# main.net
KiCad netlist of a schematic drawn in Altium Designer
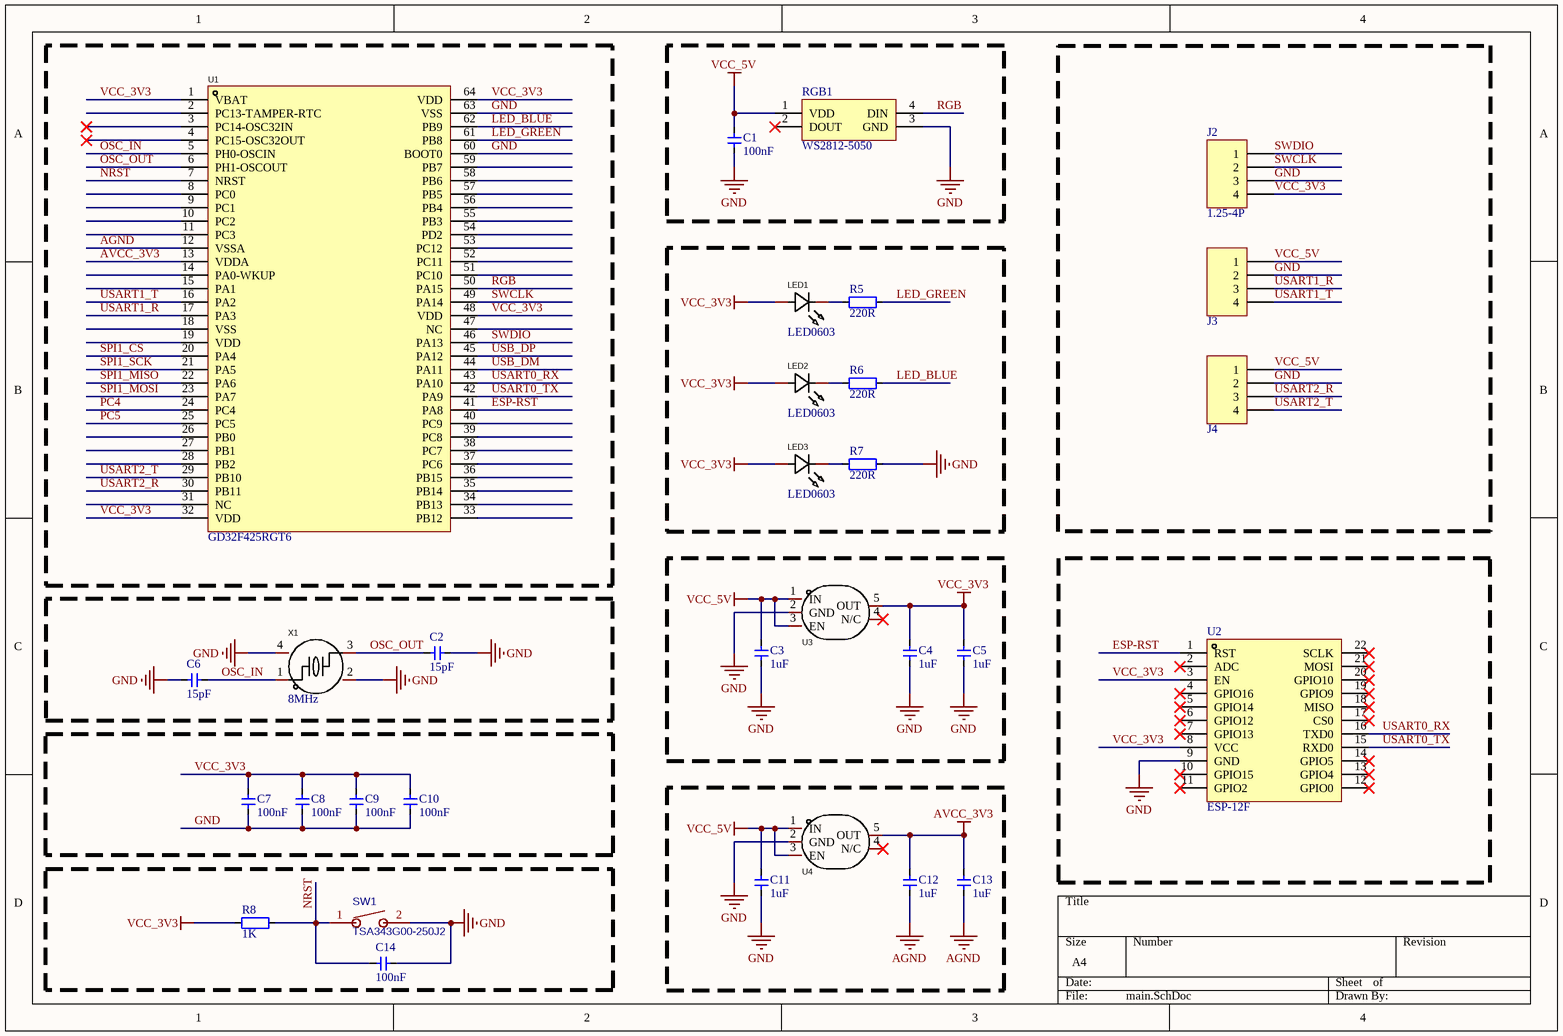
[diagram p0: main.SchDoc]

(export (version "E")
  (design (tool "Eeschema 10.0.6"))
  (components
    (comp (ref "C1") (value "100nF") (footprint "C0603") (libsource (lib "vesc6") (part "C0603")))
    (comp (ref "C2") (value "15pF") (footprint "C0603") (libsource (lib "vesc6") (part "C0603")))
    (comp (ref "C3") (value "1uF") (footprint "C0603") (libsource (lib "vesc6") (part "C0603")))
    (comp (ref "C4") (value "1uF") (footprint "C0603") (libsource (lib "vesc6") (part "C0603")))
    (comp (ref "C5") (value "1uF") (footprint "C0603") (libsource (lib "vesc6") (part "C0603")))
    (comp (ref "C6") (value "15pF") (footprint "C0603") (libsource (lib "vesc6") (part "C0603")))
    (comp (ref "C7") (value "100nF") (footprint "C0603") (libsource (lib "vesc6") (part "C0603")))
    (comp (ref "C8") (value "100nF") (footprint "C0603") (libsource (lib "vesc6") (part "C0603")))
    (comp (ref "C9") (value "100nF") (footprint "C0603") (libsource (lib "vesc6") (part "C0603")))
    (comp (ref "C10") (value "100nF") (footprint "C0603") (libsource (lib "vesc6") (part "C0603")))
    (comp (ref "C11") (value "1uF") (footprint "C0603") (libsource (lib "vesc6") (part "C0603")))
    (comp (ref "C12") (value "1uF") (footprint "C0603") (libsource (lib "vesc6") (part "C0603")))
    (comp (ref "C13") (value "1uF") (footprint "C0603") (libsource (lib "vesc6") (part "C0603")))
    (comp (ref "C14") (value "100nF") (footprint "C0603") (libsource (lib "vesc6") (part "C0603")))
    (comp (ref "J2")
      (value "1.25-4P")
      (footprint "CONN-SMD_1.25-4PWT")
      (libsource (lib "Connector") (part "A1.25-4P"))
    )
    (comp (ref "J3")
      (value "GH1.25-W-4P")
      (footprint "CONN-SMD_4P-P1.25_X1251WRS-04HF-LPSW")
      (libsource (lib "Connector") (part "GH1.25-W-4P"))
    )
    (comp (ref "J4")
      (value "GH1.25-W-4P")
      (footprint "CONN-SMD_4P-P1.25_X1251WRS-04HF-LPSW")
      (libsource (lib "Connector") (part "GH1.25-W-4P"))
    )
    (comp (ref "LED1")
      (value "LED0603")
      (footprint "LED0603-BLUE")
      (fields (field (name "MANUFACTURER") "VISHAY(威世)") (field (name "MANUFACTURER PART") "VLMTG1401-GS08"))
      (libsource (lib "vesc6") (part "LED0603"))
    )
    (comp (ref "LED2")
      (value "LED0603")
      (footprint "LED0603-BLUE")
      (fields (field (name "MANUFACTURER") "VISHAY(威世)") (field (name "MANUFACTURER PART") "VLMTG1401-GS08"))
      (libsource (lib "vesc6") (part "LED0603"))
    )
    (comp (ref "LED3")
      (value "LED0603")
      (footprint "LED0603-BLUE")
      (fields (field (name "MANUFACTURER") "VISHAY(威世)") (field (name "MANUFACTURER PART") "VLMTG1401-GS08"))
      (libsource (lib "vesc6") (part "LED0603"))
    )
    (comp (ref "R5") (value "220R") (footprint "R0603") (libsource (lib "vesc6") (part "R0603")))
    (comp (ref "R6") (value "220R") (footprint "R0603") (libsource (lib "vesc6") (part "R0603")))
    (comp (ref "R7") (value "220R") (footprint "R0603") (libsource (lib "vesc6") (part "R0603")))
    (comp (ref "R8") (value "1K") (footprint "R0603") (libsource (lib "vesc6") (part "R0603")))
    (comp (ref "RGB1")
      (value "WS2812-5050")
      (footprint "LED-SMD_4P-L5.0-W5.0-TL_WS2812B-B")
      (libsource (lib "other") (part "WS2812-5050"))
    )
    (comp (ref "SW1")
      (value "TSA343G00-250J2")
      (footprint "SW-SMD_L4.0-W2.9-LS5.0")
      (description "贴片轻触开关")
      (fields (field (name "BOM_SUPPLIER PART") "C354946") (field (name "CONTRIBUTOR") "LCSC"))
      (libsource (lib "MyLib") (part "TSA343G00-250J2"))
    )
    (comp (ref "U1")
      (value "GD32F425RGT6")
      (footprint "LQFP-64_L10.0-W10.0-P0.50-LS12.0-BL - duplicate")
      (fields (field (name "MANUFACTURER") "GigaDevice(兆易创新)"))
      (libsource (lib "IC") (part "GD32F425RGT6"))
    )
    (comp (ref "U2")
      (value "ESP-12F")
      (footprint "WIFIM-SMD_ESP-12F-ESP8266MOD")
      (libsource (lib "IC") (part "ESP-12F"))
    )
    (comp (ref "U3")
      (value "LP5907")
      (footprint "SOT-23-5_L2.9-W1.6-P0.95-LS2.8-BR")
      (fields
        (field (name "MANUFACTURER") "TI(德州仪器)")
        (field (name "MANUFACTURER PART") "LP5907MFX-3.2/NOPB")
      )
      (libsource (lib "vesc6") (part "LP5907"))
    )
    (comp (ref "U4")
      (value "LP5907")
      (footprint "SOT-23-5_L2.9-W1.6-P0.95-LS2.8-BR")
      (fields
        (field (name "MANUFACTURER") "TI(德州仪器)")
        (field (name "MANUFACTURER PART") "LP5907MFX-3.2/NOPB")
      )
      (libsource (lib "vesc6") (part "LP5907"))
    )
    (comp (ref "X1")
      (value "8MHz")
      (footprint "CRYSTAL-SMD_4P-L3.2-W2.5-BL-1")
      (fields
        (field (name "MANUFACTURER") "CJ(江苏长电/长晶)")
        (field (name "MANUFACTURER PART") "CJ13-080001210C30")
      )
      (libsource (lib "vesc6") (part "8Mhz"))
    )
  )
  (nets
    (net (code "1") (name "/ESP-RST") (class "Default")
      (node (ref "U1") (pin "41") (pinfunction "PA8_41") (pintype "passive"))
      (node (ref "U2") (pin "1") (pinfunction "RST_1") (pintype "passive"))
    )
    (net (code "2") (name "/LED_BLUE") (class "Default")
      (node (ref "R6") (pin "2") (pinfunction "2_2") (pintype "passive"))
      (node (ref "U1") (pin "62") (pinfunction "PB9_62") (pintype "passive"))
    )
    (net (code "3") (name "/LED_GREEN") (class "Default")
      (node (ref "R5") (pin "2") (pinfunction "2_2") (pintype "passive"))
      (node (ref "U1") (pin "61") (pinfunction "PB8_61") (pintype "passive"))
    )
    (net (code "4") (name "/NRST") (class "Default")
      (node (ref "C14") (pin "1") (pinfunction "1_1") (pintype "passive"))
      (node (ref "R8") (pin "2") (pinfunction "2_2") (pintype "passive"))
      (node (ref "SW1") (pin "1") (pinfunction "1_1") (pintype "passive"))
      (node (ref "U1") (pin "7") (pinfunction "NRST_7") (pintype "passive"))
    )
    (net (code "5") (name "/OSC_IN") (class "Default")
      (node (ref "C6") (pin "2") (pinfunction "2_2") (pintype "passive"))
      (node (ref "U1") (pin "5") (pinfunction "PH0-OSCIN_5") (pintype "passive"))
      (node (ref "X1") (pin "1") (pinfunction "1_1") (pintype "passive"))
    )
    (net (code "6") (name "/OSC_OUT") (class "Default")
      (node (ref "C2") (pin "1") (pinfunction "1_1") (pintype "passive"))
      (node (ref "U1") (pin "6") (pinfunction "PH1-OSCOUT_6") (pintype "passive"))
      (node (ref "X1") (pin "3") (pinfunction "3_3") (pintype "passive"))
    )
    (net (code "7") (name "/PC4") (class "Default")
      (node (ref "U1") (pin "24") (pinfunction "PC4_24") (pintype "passive"))
    )
    (net (code "8") (name "/PC5") (class "Default")
      (node (ref "U1") (pin "25") (pinfunction "PC5_25") (pintype "passive"))
    )
    (net (code "9") (name "/RGB") (class "Default")
      (node (ref "RGB1") (pin "4") (pinfunction "DIN_4") (pintype "passive"))
      (node (ref "U1") (pin "50") (pinfunction "PA15_50") (pintype "passive"))
    )
    (net (code "10") (name "/SPI1_CS") (class "Default")
      (node (ref "U1") (pin "20") (pinfunction "PA4_20") (pintype "passive"))
    )
    (net (code "11") (name "/SPI1_MISO") (class "Default")
      (node (ref "U1") (pin "22") (pinfunction "PA6_22") (pintype "passive"))
    )
    (net (code "12") (name "/SPI1_MOSI") (class "Default")
      (node (ref "U1") (pin "23") (pinfunction "PA7_23") (pintype "passive"))
    )
    (net (code "13") (name "/SPI1_SCK") (class "Default")
      (node (ref "U1") (pin "21") (pinfunction "PA5_21") (pintype "passive"))
    )
    (net (code "14") (name "/SWCLK") (class "Default")
      (node (ref "J2") (pin "2") (pinfunction "2_2") (pintype "passive"))
      (node (ref "U1") (pin "49") (pinfunction "PA14_49") (pintype "passive"))
    )
    (net (code "15") (name "/SWDIO") (class "Default")
      (node (ref "J2") (pin "1") (pinfunction "1_1") (pintype "passive"))
      (node (ref "U1") (pin "46") (pinfunction "PA13_46") (pintype "passive"))
    )
    (net (code "16") (name "/USART0_RX") (class "Default")
      (node (ref "U1") (pin "43") (pinfunction "PA10_43") (pintype "passive"))
      (node (ref "U2") (pin "16") (pinfunction "TXD0_16") (pintype "passive"))
    )
    (net (code "17") (name "/USART0_TX") (class "Default")
      (node (ref "U1") (pin "42") (pinfunction "PA9_42") (pintype "passive"))
      (node (ref "U2") (pin "15") (pinfunction "RXD0_15") (pintype "passive"))
    )
    (net (code "18") (name "/USART1_R") (class "Default")
      (node (ref "J3") (pin "3") (pinfunction "3_3") (pintype "passive"))
      (node (ref "U1") (pin "17") (pinfunction "PA3_17") (pintype "passive"))
    )
    (net (code "19") (name "/USART1_T") (class "Default")
      (node (ref "J3") (pin "4") (pinfunction "4_4") (pintype "passive"))
      (node (ref "U1") (pin "16") (pinfunction "PA2_16") (pintype "passive"))
    )
    (net (code "20") (name "/USART2_R") (class "Default")
      (node (ref "J4") (pin "3") (pinfunction "3_3") (pintype "passive"))
      (node (ref "U1") (pin "30") (pinfunction "PB11_30") (pintype "passive"))
    )
    (net (code "21") (name "/USART2_T") (class "Default")
      (node (ref "J4") (pin "4") (pinfunction "4_4") (pintype "passive"))
      (node (ref "U1") (pin "29") (pinfunction "PB10_29") (pintype "passive"))
    )
    (net (code "22") (name "/USB_DM") (class "Default")
      (node (ref "U1") (pin "44") (pinfunction "PA11_44") (pintype "passive"))
    )
    (net (code "23") (name "/USB_DP") (class "Default")
      (node (ref "U1") (pin "45") (pinfunction "PA12_45") (pintype "passive"))
    )
    (net (code "24") (name "AGND") (class "Default")
      (node (ref "C12") (pin "1") (pinfunction "1_1") (pintype "passive"))
      (node (ref "C13") (pin "1") (pinfunction "1_1") (pintype "passive"))
      (node (ref "U1") (pin "12") (pinfunction "VSSA_12") (pintype "passive"))
    )
    (net (code "25") (name "AVCC_3V3") (class "Default")
      (node (ref "C12") (pin "2") (pinfunction "2_2") (pintype "passive"))
      (node (ref "C13") (pin "2") (pinfunction "2_2") (pintype "passive"))
      (node (ref "U1") (pin "13") (pinfunction "VDDA_13") (pintype "passive"))
      (node (ref "U4") (pin "5") (pinfunction "OUT_5") (pintype "passive"))
    )
    (net (code "26") (name "GND") (class "Default")
      (node (ref "C1") (pin "1") (pinfunction "1_1") (pintype "passive"))
      (node (ref "C10") (pin "1") (pinfunction "1_1") (pintype "passive"))
      (node (ref "C11") (pin "1") (pinfunction "1_1") (pintype "passive"))
      (node (ref "C14") (pin "2") (pinfunction "2_2") (pintype "passive"))
      (node (ref "C2") (pin "2") (pinfunction "2_2") (pintype "passive"))
      (node (ref "C3") (pin "1") (pinfunction "1_1") (pintype "passive"))
      (node (ref "C4") (pin "1") (pinfunction "1_1") (pintype "passive"))
      (node (ref "C5") (pin "1") (pinfunction "1_1") (pintype "passive"))
      (node (ref "C6") (pin "1") (pinfunction "1_1") (pintype "passive"))
      (node (ref "C7") (pin "1") (pinfunction "1_1") (pintype "passive"))
      (node (ref "C8") (pin "1") (pinfunction "1_1") (pintype "passive"))
      (node (ref "C9") (pin "1") (pinfunction "1_1") (pintype "passive"))
      (node (ref "J2") (pin "3") (pinfunction "3_3") (pintype "passive"))
      (node (ref "J3") (pin "2") (pinfunction "2_2") (pintype "passive"))
      (node (ref "J4") (pin "2") (pinfunction "2_2") (pintype "passive"))
      (node (ref "R7") (pin "2") (pinfunction "2_2") (pintype "passive"))
      (node (ref "RGB1") (pin "3") (pinfunction "GND_3") (pintype "passive"))
      (node (ref "SW1") (pin "2") (pinfunction "2_2") (pintype "passive"))
      (node (ref "U1") (pin "60") (pinfunction "BOOT0_60") (pintype "passive"))
      (node (ref "U1") (pin "63") (pinfunction "VSS_63") (pintype "passive"))
      (node (ref "U2") (pin "9") (pinfunction "GND_9") (pintype "passive"))
      (node (ref "U3") (pin "2") (pinfunction "GND_2") (pintype "passive"))
      (node (ref "U4") (pin "2") (pinfunction "GND_2") (pintype "passive"))
      (node (ref "X1") (pin "2") (pinfunction "GND_2") (pintype "passive"))
      (node (ref "X1") (pin "4") (pinfunction "GND_4") (pintype "passive"))
    )
    (net (code "27") (name "Net-(LED1-K)") (class "Default")
      (node (ref "LED1") (pin "1") (pinfunction "K_1") (pintype "passive"))
      (node (ref "R5") (pin "1") (pinfunction "1_1") (pintype "passive"))
    )
    (net (code "28") (name "Net-(LED2-K)") (class "Default")
      (node (ref "LED2") (pin "1") (pinfunction "K_1") (pintype "passive"))
      (node (ref "R6") (pin "1") (pinfunction "1_1") (pintype "passive"))
    )
    (net (code "29") (name "Net-(LED3-K)") (class "Default")
      (node (ref "LED3") (pin "1") (pinfunction "K_1") (pintype "passive"))
      (node (ref "R7") (pin "1") (pinfunction "1_1") (pintype "passive"))
    )
    (net (code "30") (name "VCC_3V3") (class "Default")
      (node (ref "C10") (pin "2") (pinfunction "2_2") (pintype "passive"))
      (node (ref "C4") (pin "2") (pinfunction "2_2") (pintype "passive"))
      (node (ref "C5") (pin "2") (pinfunction "2_2") (pintype "passive"))
      (node (ref "C7") (pin "2") (pinfunction "2_2") (pintype "passive"))
      (node (ref "C8") (pin "2") (pinfunction "2_2") (pintype "passive"))
      (node (ref "C9") (pin "2") (pinfunction "2_2") (pintype "passive"))
      (node (ref "J2") (pin "4") (pinfunction "4_4") (pintype "passive"))
      (node (ref "LED1") (pin "2") (pinfunction "A_2") (pintype "passive"))
      (node (ref "LED2") (pin "2") (pinfunction "A_2") (pintype "passive"))
      (node (ref "LED3") (pin "2") (pinfunction "A_2") (pintype "passive"))
      (node (ref "R8") (pin "1") (pinfunction "1_1") (pintype "passive"))
      (node (ref "U1") (pin "1") (pinfunction "VBAT_1") (pintype "passive"))
      (node (ref "U1") (pin "32") (pinfunction "VDD_32") (pintype "passive"))
      (node (ref "U1") (pin "48") (pinfunction "VDD_48") (pintype "passive"))
      (node (ref "U1") (pin "64") (pinfunction "VDD_64") (pintype "passive"))
      (node (ref "U2") (pin "3") (pinfunction "EN_3") (pintype "passive"))
      (node (ref "U2") (pin "8") (pinfunction "VCC_8") (pintype "passive"))
      (node (ref "U3") (pin "5") (pinfunction "OUT_5") (pintype "passive"))
    )
    (net (code "31") (name "VCC_5V") (class "Default")
      (node (ref "C1") (pin "2") (pinfunction "2_2") (pintype "passive"))
      (node (ref "C11") (pin "2") (pinfunction "2_2") (pintype "passive"))
      (node (ref "C3") (pin "2") (pinfunction "2_2") (pintype "passive"))
      (node (ref "J3") (pin "1") (pinfunction "1_1") (pintype "passive"))
      (node (ref "J4") (pin "1") (pinfunction "1_1") (pintype "passive"))
      (node (ref "RGB1") (pin "1") (pinfunction "VDD_1") (pintype "passive"))
      (node (ref "U3") (pin "1") (pinfunction "IN_1") (pintype "passive"))
      (node (ref "U3") (pin "3") (pinfunction "EN_3") (pintype "passive"))
      (node (ref "U4") (pin "1") (pinfunction "IN_1") (pintype "passive"))
      (node (ref "U4") (pin "3") (pinfunction "EN_3") (pintype "passive"))
    )
    (net (code "32") (name "unconnected-(RGB1-DOUT-Pad2)") (class "Default")
      (node (ref "RGB1") (pin "2") (pinfunction "DOUT_2") (pintype "passive+no_connect"))
    )
    (net (code "33") (name "unconnected-(U1-NC-Pad31)") (class "Default")
      (node (ref "U1") (pin "31") (pinfunction "NC_31") (pintype "passive"))
    )
    (net (code "34") (name "unconnected-(U1-NC-Pad47)") (class "Default")
      (node (ref "U1") (pin "47") (pinfunction "NC_47") (pintype "passive"))
    )
    (net (code "35") (name "unconnected-(U1-PA0-WKUP-Pad14)") (class "Default")
      (node (ref "U1") (pin "14") (pinfunction "PA0-WKUP_14") (pintype "passive"))
    )
    (net (code "36") (name "unconnected-(U1-PA1-Pad15)") (class "Default")
      (node (ref "U1") (pin "15") (pinfunction "PA1_15") (pintype "passive"))
    )
    (net (code "37") (name "unconnected-(U1-PB0-Pad26)") (class "Default")
      (node (ref "U1") (pin "26") (pinfunction "PB0_26") (pintype "passive"))
    )
    (net (code "38") (name "unconnected-(U1-PB1-Pad27)") (class "Default")
      (node (ref "U1") (pin "27") (pinfunction "PB1_27") (pintype "passive"))
    )
    (net (code "39") (name "unconnected-(U1-PB2-Pad28)") (class "Default")
      (node (ref "U1") (pin "28") (pinfunction "PB2_28") (pintype "passive"))
    )
    (net (code "40") (name "unconnected-(U1-PB3-Pad55)") (class "Default")
      (node (ref "U1") (pin "55") (pinfunction "PB3_55") (pintype "passive"))
    )
    (net (code "41") (name "unconnected-(U1-PB4-Pad56)") (class "Default")
      (node (ref "U1") (pin "56") (pinfunction "PB4_56") (pintype "passive"))
    )
    (net (code "42") (name "unconnected-(U1-PB5-Pad57)") (class "Default")
      (node (ref "U1") (pin "57") (pinfunction "PB5_57") (pintype "passive"))
    )
    (net (code "43") (name "unconnected-(U1-PB6-Pad58)") (class "Default")
      (node (ref "U1") (pin "58") (pinfunction "PB6_58") (pintype "passive"))
    )
    (net (code "44") (name "unconnected-(U1-PB7-Pad59)") (class "Default")
      (node (ref "U1") (pin "59") (pinfunction "PB7_59") (pintype "passive"))
    )
    (net (code "45") (name "unconnected-(U1-PB12-Pad33)") (class "Default")
      (node (ref "U1") (pin "33") (pinfunction "PB12_33") (pintype "passive"))
    )
    (net (code "46") (name "unconnected-(U1-PB13-Pad34)") (class "Default")
      (node (ref "U1") (pin "34") (pinfunction "PB13_34") (pintype "passive"))
    )
    (net (code "47") (name "unconnected-(U1-PB14-Pad35)") (class "Default")
      (node (ref "U1") (pin "35") (pinfunction "PB14_35") (pintype "passive"))
    )
    (net (code "48") (name "unconnected-(U1-PB15-Pad36)") (class "Default")
      (node (ref "U1") (pin "36") (pinfunction "PB15_36") (pintype "passive"))
    )
    (net (code "49") (name "unconnected-(U1-PC0-Pad8)") (class "Default")
      (node (ref "U1") (pin "8") (pinfunction "PC0_8") (pintype "passive"))
    )
    (net (code "50") (name "unconnected-(U1-PC1-Pad9)") (class "Default")
      (node (ref "U1") (pin "9") (pinfunction "PC1_9") (pintype "passive"))
    )
    (net (code "51") (name "unconnected-(U1-PC2-Pad10)") (class "Default")
      (node (ref "U1") (pin "10") (pinfunction "PC2_10") (pintype "passive"))
    )
    (net (code "52") (name "unconnected-(U1-PC3-Pad11)") (class "Default")
      (node (ref "U1") (pin "11") (pinfunction "PC3_11") (pintype "passive"))
    )
    (net (code "53") (name "unconnected-(U1-PC6-Pad37)") (class "Default")
      (node (ref "U1") (pin "37") (pinfunction "PC6_37") (pintype "passive"))
    )
    (net (code "54") (name "unconnected-(U1-PC7-Pad38)") (class "Default")
      (node (ref "U1") (pin "38") (pinfunction "PC7_38") (pintype "passive"))
    )
    (net (code "55") (name "unconnected-(U1-PC8-Pad39)") (class "Default")
      (node (ref "U1") (pin "39") (pinfunction "PC8_39") (pintype "passive"))
    )
    (net (code "56") (name "unconnected-(U1-PC9-Pad40)") (class "Default")
      (node (ref "U1") (pin "40") (pinfunction "PC9_40") (pintype "passive"))
    )
    (net (code "57") (name "unconnected-(U1-PC10-Pad51)") (class "Default")
      (node (ref "U1") (pin "51") (pinfunction "PC10_51") (pintype "passive"))
    )
    (net (code "58") (name "unconnected-(U1-PC11-Pad52)") (class "Default")
      (node (ref "U1") (pin "52") (pinfunction "PC11_52") (pintype "passive"))
    )
    (net (code "59") (name "unconnected-(U1-PC12-Pad53)") (class "Default")
      (node (ref "U1") (pin "53") (pinfunction "PC12_53") (pintype "passive"))
    )
    (net (code "60") (name "unconnected-(U1-PC13-TAMPER-RTC-Pad2)") (class "Default")
      (node (ref "U1") (pin "2") (pinfunction "PC13-TAMPER-RTC_2") (pintype "passive"))
    )
    (net (code "61") (name "unconnected-(U1-PC14-OSC32IN-Pad3)") (class "Default")
      (node (ref "U1") (pin "3") (pinfunction "PC14-OSC32IN_3") (pintype "passive+no_connect"))
    )
    (net (code "62") (name "unconnected-(U1-PC15-OSC32OUT-Pad4)") (class "Default")
      (node (ref "U1") (pin "4") (pinfunction "PC15-OSC32OUT_4") (pintype "passive+no_connect"))
    )
    (net (code "63") (name "unconnected-(U1-PD2-Pad54)") (class "Default")
      (node (ref "U1") (pin "54") (pinfunction "PD2_54") (pintype "passive"))
    )
    (net (code "64") (name "unconnected-(U1-VDD-Pad19)") (class "Default")
      (node (ref "U1") (pin "19") (pinfunction "VDD_19") (pintype "passive"))
    )
    (net (code "65") (name "unconnected-(U1-VSS-Pad18)") (class "Default")
      (node (ref "U1") (pin "18") (pinfunction "VSS_18") (pintype "passive"))
    )
    (net (code "66") (name "unconnected-(U2-ADC-Pad2)") (class "Default")
      (node (ref "U2") (pin "2") (pinfunction "ADC_2") (pintype "passive+no_connect"))
    )
    (net (code "67") (name "unconnected-(U2-CS0-Pad17)") (class "Default")
      (node (ref "U2") (pin "17") (pinfunction "CS0_17") (pintype "passive+no_connect"))
    )
    (net (code "68") (name "unconnected-(U2-GPIO0-Pad12)") (class "Default")
      (node (ref "U2") (pin "12") (pinfunction "GPIO0_12") (pintype "passive+no_connect"))
    )
    (net (code "69") (name "unconnected-(U2-GPIO2-Pad11)") (class "Default")
      (node (ref "U2") (pin "11") (pinfunction "GPIO2_11") (pintype "passive+no_connect"))
    )
    (net (code "70") (name "unconnected-(U2-GPIO4-Pad13)") (class "Default")
      (node (ref "U2") (pin "13") (pinfunction "GPIO4_13") (pintype "passive+no_connect"))
    )
    (net (code "71") (name "unconnected-(U2-GPIO5-Pad14)") (class "Default")
      (node (ref "U2") (pin "14") (pinfunction "GPIO5_14") (pintype "passive+no_connect"))
    )
    (net (code "72") (name "unconnected-(U2-GPIO9-Pad19)") (class "Default")
      (node (ref "U2") (pin "19") (pinfunction "GPIO9_19") (pintype "passive+no_connect"))
    )
    (net (code "73") (name "unconnected-(U2-GPIO10-Pad20)") (class "Default")
      (node (ref "U2") (pin "20") (pinfunction "GPIO10_20") (pintype "passive+no_connect"))
    )
    (net (code "74") (name "unconnected-(U2-GPIO12-Pad6)") (class "Default")
      (node (ref "U2") (pin "6") (pinfunction "GPIO12_6") (pintype "passive+no_connect"))
    )
    (net (code "75") (name "unconnected-(U2-GPIO13-Pad7)") (class "Default")
      (node (ref "U2") (pin "7") (pinfunction "GPIO13_7") (pintype "passive+no_connect"))
    )
    (net (code "76") (name "unconnected-(U2-GPIO14-Pad5)") (class "Default")
      (node (ref "U2") (pin "5") (pinfunction "GPIO14_5") (pintype "passive+no_connect"))
    )
    (net (code "77") (name "unconnected-(U2-GPIO15-Pad10)") (class "Default")
      (node (ref "U2") (pin "10") (pinfunction "GPIO15_10") (pintype "passive+no_connect"))
    )
    (net (code "78") (name "unconnected-(U2-GPIO16-Pad4)") (class "Default")
      (node (ref "U2") (pin "4") (pinfunction "GPIO16_4") (pintype "passive+no_connect"))
    )
    (net (code "79") (name "unconnected-(U2-MISO-Pad18)") (class "Default")
      (node (ref "U2") (pin "18") (pinfunction "MISO_18") (pintype "passive+no_connect"))
    )
    (net (code "80") (name "unconnected-(U2-MOSI-Pad21)") (class "Default")
      (node (ref "U2") (pin "21") (pinfunction "MOSI_21") (pintype "passive+no_connect"))
    )
    (net (code "81") (name "unconnected-(U2-SCLK-Pad22)") (class "Default")
      (node (ref "U2") (pin "22") (pinfunction "SCLK_22") (pintype "passive+no_connect"))
    )
    (net (code "82") (name "unconnected-(U3-N{slash}C-Pad4)") (class "Default")
      (node (ref "U3") (pin "4") (pinfunction "N/C_4") (pintype "passive+no_connect"))
    )
    (net (code "83") (name "unconnected-(U4-N{slash}C-Pad4)") (class "Default")
      (node (ref "U4") (pin "4") (pinfunction "N/C_4") (pintype "passive+no_connect"))
    )
  )
)
